# 5vOutputs.net
KiCad netlist of a schematic drawn in Altium Designer
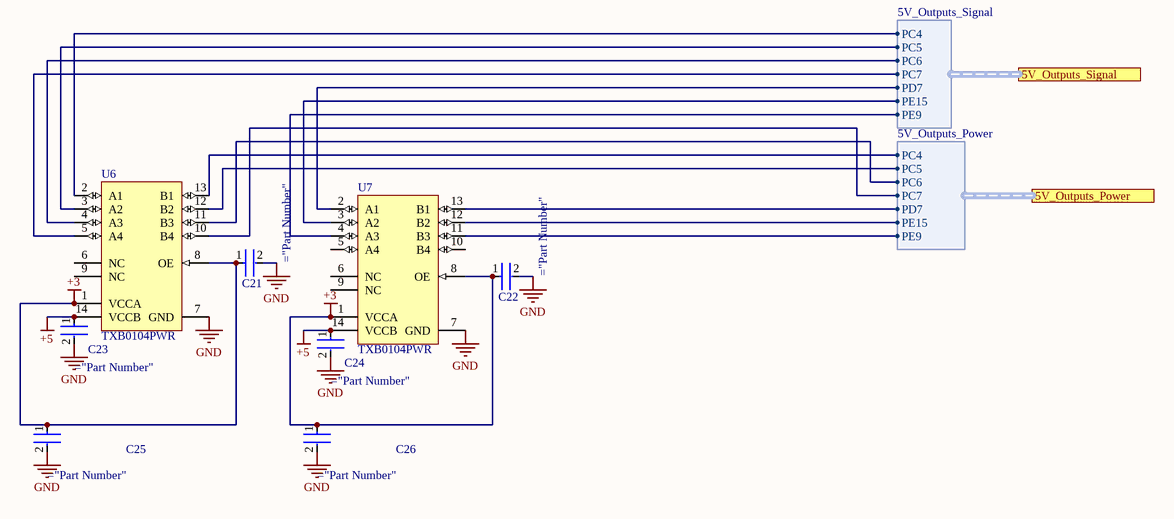
[diagram p0: 5vOutputs.SchDoc]

(export (version "E")
  (design (tool "Eeschema 10.0.6"))
  (components
    (comp (ref "C21")
      (value "C0603C104K5RACTU")
      (footprint "Kemet_C0805_IPC_A")
      (libsource (lib "UNK_Kemet_C0603C104K5RACTU_eec") (part "C0603C104K5RACTU"))
    )
    (comp (ref "C22")
      (value "C0603C104K5RACTU")
      (footprint "Kemet_C0805_IPC_A")
      (libsource (lib "UNK_Kemet_C0603C104K5RACTU_eec") (part "C0603C104K5RACTU"))
    )
    (comp (ref "C23")
      (value "C0603C104K5RACTU")
      (footprint "Kemet_C0805_IPC_A")
      (libsource (lib "UNK_Kemet_C0603C104K5RACTU_eec") (part "C0603C104K5RACTU"))
    )
    (comp (ref "C24")
      (value "C0603C104K5RACTU")
      (footprint "Kemet_C0805_IPC_A")
      (libsource (lib "UNK_Kemet_C0603C104K5RACTU_eec") (part "C0603C104K5RACTU"))
    )
    (comp (ref "C25")
      (value "C0603C104K5RACTU")
      (footprint "Kemet_C0805_IPC_A")
      (libsource (lib "UNK_Kemet_C0603C104K5RACTU_eec") (part "C0603C104K5RACTU"))
    )
    (comp (ref "C26")
      (value "C0603C104K5RACTU")
      (footprint "Kemet_C0805_IPC_A")
      (libsource (lib "UNK_Kemet_C0603C104K5RACTU_eec") (part "C0603C104K5RACTU"))
    )
    (comp (ref "U6")
      (value "TXB0104PWR")
      (footprint "PW0014A_Custom")
      (fields (field (name "MANUFACTURER") "Texas Instruments"))
      (libsource (lib "Components - 19.05.19 - 16.35") (part "TI-TXB0104-TSSOP_PW-14"))
    )
    (comp (ref "U7")
      (value "TXB0104PWR")
      (footprint "PW0014A_Custom")
      (fields (field (name "MANUFACTURER") "Texas Instruments"))
      (libsource (lib "Components - 19.05.19 - 16.35") (part "TI-TXB0104-TSSOP_PW-14"))
    )
  )
  (nets
    (net (code "3") (name "+3") (class "Default")
      (node (ref "C21") (pin "1") (pinfunction "1_1") (pintype "passive"))
      (node (ref "C22") (pin "1") (pinfunction "1_1") (pintype "passive"))
      (node (ref "C25") (pin "1") (pinfunction "1_1") (pintype "passive"))
      (node (ref "C26") (pin "1") (pinfunction "1_1") (pintype "passive"))
      (node (ref "U6") (pin "1") (pinfunction "VCCA_1") (pintype "power_in"))
      (node (ref "U6") (pin "8") (pinfunction "OE_8") (pintype "input"))
      (node (ref "U7") (pin "1") (pinfunction "VCCA_1") (pintype "power_in"))
      (node (ref "U7") (pin "8") (pinfunction "OE_8") (pintype "input"))
    )
    (net (code "4") (name "+5") (class "Default")
      (node (ref "C23") (pin "1") (pinfunction "1_1") (pintype "passive"))
      (node (ref "C24") (pin "1") (pinfunction "1_1") (pintype "passive"))
      (node (ref "U6") (pin "14") (pinfunction "VCCB_14") (pintype "power_in"))
      (node (ref "U7") (pin "14") (pinfunction "VCCB_14") (pintype "power_in"))
    )
    (net (code "7") (name "GND") (class "Default")
      (node (ref "C21") (pin "2") (pinfunction "2_2") (pintype "passive"))
      (node (ref "C22") (pin "2") (pinfunction "2_2") (pintype "passive"))
      (node (ref "C23") (pin "2") (pinfunction "2_2") (pintype "passive"))
      (node (ref "C24") (pin "2") (pinfunction "2_2") (pintype "passive"))
      (node (ref "C25") (pin "2") (pinfunction "2_2") (pintype "passive"))
      (node (ref "C26") (pin "2") (pinfunction "2_2") (pintype "passive"))
      (node (ref "U6") (pin "7") (pinfunction "GND_7") (pintype "power_in"))
      (node (ref "U7") (pin "7") (pinfunction "GND_7") (pintype "power_in"))
    )
    (net (code "8") (name "unconnected-(U6-A1-Pad2)") (class "Default")
      (node (ref "U6") (pin "2") (pinfunction "A1_2") (pintype "bidirectional"))
    )
    (net (code "9") (name "unconnected-(U6-A2-Pad3)") (class "Default")
      (node (ref "U6") (pin "3") (pinfunction "A2_3") (pintype "bidirectional"))
    )
    (net (code "10") (name "unconnected-(U6-A3-Pad4)") (class "Default")
      (node (ref "U6") (pin "4") (pinfunction "A3_4") (pintype "bidirectional"))
    )
    (net (code "11") (name "unconnected-(U6-A4-Pad5)") (class "Default")
      (node (ref "U6") (pin "5") (pinfunction "A4_5") (pintype "bidirectional"))
    )
    (net (code "12") (name "unconnected-(U6-B1-Pad13)") (class "Default")
      (node (ref "U6") (pin "13") (pinfunction "B1_13") (pintype "bidirectional"))
    )
    (net (code "13") (name "unconnected-(U6-B2-Pad12)") (class "Default")
      (node (ref "U6") (pin "12") (pinfunction "B2_12") (pintype "bidirectional"))
    )
    (net (code "14") (name "unconnected-(U6-B3-Pad11)") (class "Default")
      (node (ref "U6") (pin "11") (pinfunction "B3_11") (pintype "bidirectional"))
    )
    (net (code "15") (name "unconnected-(U6-B4-Pad10)") (class "Default")
      (node (ref "U6") (pin "10") (pinfunction "B4_10") (pintype "bidirectional"))
    )
    (net (code "16") (name "unconnected-(U6-NC-Pad6)") (class "Default")
      (node (ref "U6") (pin "6") (pinfunction "NC_6") (pintype "passive"))
    )
    (net (code "17") (name "unconnected-(U6-NC-Pad9)") (class "Default")
      (node (ref "U6") (pin "9") (pinfunction "NC_9") (pintype "passive"))
    )
    (net (code "18") (name "unconnected-(U7-A1-Pad2)") (class "Default")
      (node (ref "U7") (pin "2") (pinfunction "A1_2") (pintype "bidirectional"))
    )
    (net (code "19") (name "unconnected-(U7-A2-Pad3)") (class "Default")
      (node (ref "U7") (pin "3") (pinfunction "A2_3") (pintype "bidirectional"))
    )
    (net (code "20") (name "unconnected-(U7-A3-Pad4)") (class "Default")
      (node (ref "U7") (pin "4") (pinfunction "A3_4") (pintype "bidirectional"))
    )
    (net (code "21") (name "unconnected-(U7-A4-Pad5)") (class "Default")
      (node (ref "U7") (pin "5") (pinfunction "A4_5") (pintype "bidirectional"))
    )
    (net (code "22") (name "unconnected-(U7-B1-Pad13)") (class "Default")
      (node (ref "U7") (pin "13") (pinfunction "B1_13") (pintype "bidirectional"))
    )
    (net (code "23") (name "unconnected-(U7-B2-Pad12)") (class "Default")
      (node (ref "U7") (pin "12") (pinfunction "B2_12") (pintype "bidirectional"))
    )
    (net (code "24") (name "unconnected-(U7-B3-Pad11)") (class "Default")
      (node (ref "U7") (pin "11") (pinfunction "B3_11") (pintype "bidirectional"))
    )
    (net (code "25") (name "unconnected-(U7-B4-Pad10)") (class "Default")
      (node (ref "U7") (pin "10") (pinfunction "B4_10") (pintype "bidirectional"))
    )
    (net (code "26") (name "unconnected-(U7-NC-Pad6)") (class "Default")
      (node (ref "U7") (pin "6") (pinfunction "NC_6") (pintype "passive"))
    )
    (net (code "27") (name "unconnected-(U7-NC-Pad9)") (class "Default")
      (node (ref "U7") (pin "9") (pinfunction "NC_9") (pintype "passive"))
    )
  )
)
